# i2c-7segled-SOIC.net
KiCad netlist of a schematic drawn in EAGLE
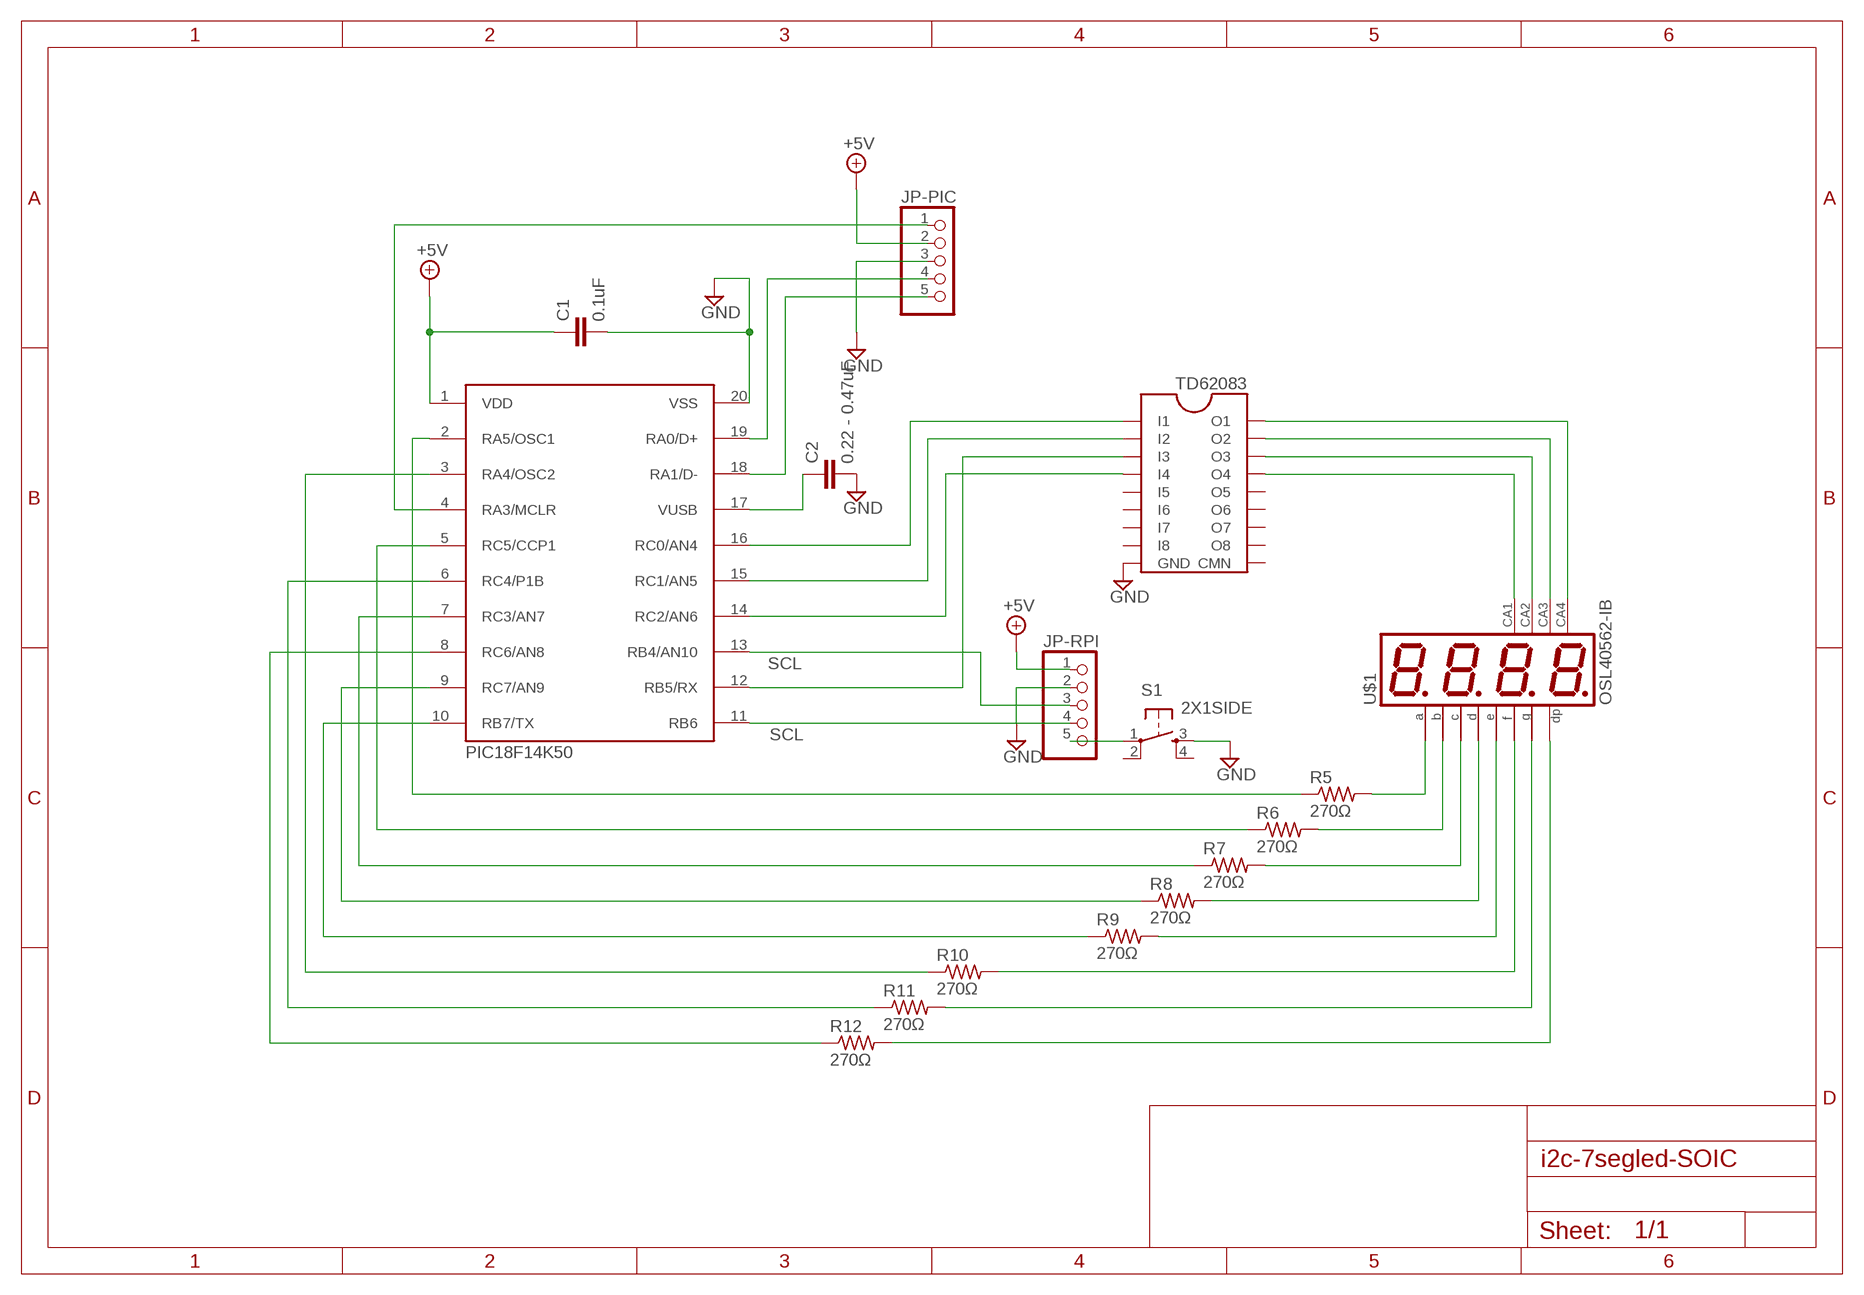
[diagram p0: schematic, sheet 1]

(export (version "E")
  (design (tool "Eeschema 10.0.6"))
  (components
    (comp (ref "C1")
      (value "0.1uF")
      (footprint "eagle-import:C0504")
      (libsource (lib "eagle-import") (part "C-EUC0504"))
    )
    (comp (ref "C2")
      (value "0.22 - 0.47uF")
      (footprint "eagle-import:C0504")
      (libsource (lib "eagle-import") (part "C-EUC0504"))
    )
    (comp (ref "JP-PIC")
      (value "PINHD-1X5")
      (footprint "eagle-import:1X05")
      (libsource (lib "eagle-import") (part "PINHD-1X5"))
    )
    (comp (ref "JP-RPI")
      (value "PINHD-1X5")
      (footprint "eagle-import:1X05")
      (libsource (lib "eagle-import") (part "PINHD-1X5"))
    )
    (comp (ref "PIC18F14K50")
      (value "PIC18F14K50-SO")
      (footprint "eagle-import:SO20")
      (libsource (lib "eagle-import") (part "PIC18F14K50-SO"))
    )
    (comp (ref "R5")
      (value "270Ω")
      (footprint "eagle-import:M0805")
      (libsource (lib "eagle-import") (part "R-US_M0805"))
    )
    (comp (ref "R6")
      (value "270Ω")
      (footprint "eagle-import:M0805")
      (libsource (lib "eagle-import") (part "R-US_M0805"))
    )
    (comp (ref "R7")
      (value "270Ω")
      (footprint "eagle-import:M0805")
      (libsource (lib "eagle-import") (part "R-US_M0805"))
    )
    (comp (ref "R8")
      (value "270Ω")
      (footprint "eagle-import:M0805")
      (libsource (lib "eagle-import") (part "R-US_M0805"))
    )
    (comp (ref "R9")
      (value "270Ω")
      (footprint "eagle-import:M0805")
      (libsource (lib "eagle-import") (part "R-US_M0805"))
    )
    (comp (ref "R10")
      (value "270Ω")
      (footprint "eagle-import:M0805")
      (libsource (lib "eagle-import") (part "R-US_M0805"))
    )
    (comp (ref "R11")
      (value "270Ω")
      (footprint "eagle-import:M0805")
      (libsource (lib "eagle-import") (part "R-US_M0805"))
    )
    (comp (ref "R12")
      (value "270Ω")
      (footprint "eagle-import:M0805")
      (libsource (lib "eagle-import") (part "R-US_M0805"))
    )
    (comp (ref "S1")
      (value "2X1SIDE")
      (footprint "eagle-import:2X1SIDE")
      (libsource (lib "eagle-import") (part "2X1SIDE"))
    )
    (comp (ref "U$1")
      (value "OSL40562-IB")
      (footprint "eagle-import:OSL40562")
      (libsource (lib "eagle-import") (part "OSL40562-?IB"))
    )
    (comp (ref "U$2")
      (value "TD62083")
      (footprint "eagle-import:SO18")
      (libsource (lib "eagle-import") (part "TD62083"))
    )
  )
  (nets
    (net (code "1") (name "+5V") (class "Default")
      (node (ref "C1") (pin "1") (pinfunction "1_1") (pintype "passive"))
      (node (ref "JP-PIC") (pin "2") (pinfunction "2_2") (pintype "passive"))
      (node (ref "JP-RPI") (pin "1") (pinfunction "1_1") (pintype "passive"))
      (node (ref "PIC18F14K50") (pin "1") (pinfunction "VDD_1") (pintype "bidirectional"))
    )
    (net (code "2") (name "/SCL") (class "Default")
      (node (ref "JP-RPI") (pin "3") (pinfunction "3_3") (pintype "passive"))
      (node (ref "PIC18F14K50") (pin "13") (pinfunction "RB4/AN10_13") (pintype "bidirectional"))
    )
    (net (code "3") (name "GND") (class "Default")
      (node (ref "C1") (pin "2") (pinfunction "2_2") (pintype "passive"))
      (node (ref "C2") (pin "2") (pinfunction "2_2") (pintype "passive"))
      (node (ref "JP-PIC") (pin "3") (pinfunction "3_3") (pintype "passive"))
      (node (ref "JP-RPI") (pin "2") (pinfunction "2_2") (pintype "passive"))
      (node (ref "PIC18F14K50") (pin "20") (pinfunction "VSS_20") (pintype "bidirectional"))
      (node (ref "S1") (pin "3") (pinfunction "S_3") (pintype "passive"))
      (node (ref "U$2") (pin "9") (pinfunction "GND_9") (pintype "passive"))
    )
    (net (code "4") (name "Net-(PIC18F14K50-RA0{slash}D+)") (class "Default")
      (node (ref "JP-PIC") (pin "4") (pinfunction "4_4") (pintype "passive"))
      (node (ref "PIC18F14K50") (pin "19") (pinfunction "RA0/D+_19") (pintype "bidirectional"))
    )
    (net (code "5") (name "Net-(PIC18F14K50-RA1{slash}D-)") (class "Default")
      (node (ref "JP-PIC") (pin "5") (pinfunction "5_5") (pintype "passive"))
      (node (ref "PIC18F14K50") (pin "18") (pinfunction "RA1/D-_18") (pintype "bidirectional"))
    )
    (net (code "6") (name "Net-(PIC18F14K50-RA3{slash}MCLR)") (class "Default")
      (node (ref "JP-PIC") (pin "1") (pinfunction "1_1") (pintype "passive"))
      (node (ref "PIC18F14K50") (pin "4") (pinfunction "RA3/MCLR_4") (pintype "bidirectional"))
    )
    (net (code "7") (name "Net-(PIC18F14K50-RA4{slash}OSC2)") (class "Default")
      (node (ref "PIC18F14K50") (pin "3") (pinfunction "RA4/OSC2_3") (pintype "bidirectional"))
      (node (ref "R10") (pin "1") (pinfunction "1_1") (pintype "passive"))
    )
    (net (code "8") (name "Net-(PIC18F14K50-RA5{slash}OSC1)") (class "Default")
      (node (ref "PIC18F14K50") (pin "2") (pinfunction "RA5/OSC1_2") (pintype "bidirectional"))
      (node (ref "R5") (pin "1") (pinfunction "1_1") (pintype "passive"))
    )
    (net (code "9") (name "Net-(PIC18F14K50-RB5{slash}RX)") (class "Default")
      (node (ref "PIC18F14K50") (pin "12") (pinfunction "RB5/RX_12") (pintype "bidirectional"))
      (node (ref "U$2") (pin "3") (pinfunction "I3_3") (pintype "passive"))
    )
    (net (code "10") (name "Net-(PIC18F14K50-RB6)") (class "Default")
      (node (ref "JP-RPI") (pin "4") (pinfunction "4_4") (pintype "passive"))
      (node (ref "PIC18F14K50") (pin "11") (pinfunction "RB6_11") (pintype "bidirectional"))
    )
    (net (code "11") (name "Net-(PIC18F14K50-RB7{slash}TX)") (class "Default")
      (node (ref "PIC18F14K50") (pin "10") (pinfunction "RB7/TX_10") (pintype "bidirectional"))
      (node (ref "R9") (pin "1") (pinfunction "1_1") (pintype "passive"))
    )
    (net (code "12") (name "Net-(PIC18F14K50-RC0{slash}AN4)") (class "Default")
      (node (ref "PIC18F14K50") (pin "16") (pinfunction "RC0/AN4_16") (pintype "bidirectional"))
      (node (ref "U$2") (pin "1") (pinfunction "I1_1") (pintype "passive"))
    )
    (net (code "13") (name "Net-(PIC18F14K50-RC1{slash}AN5)") (class "Default")
      (node (ref "PIC18F14K50") (pin "15") (pinfunction "RC1/AN5_15") (pintype "bidirectional"))
      (node (ref "U$2") (pin "2") (pinfunction "I2_2") (pintype "passive"))
    )
    (net (code "14") (name "Net-(PIC18F14K50-RC2{slash}AN6)") (class "Default")
      (node (ref "PIC18F14K50") (pin "14") (pinfunction "RC2/AN6_14") (pintype "bidirectional"))
      (node (ref "U$2") (pin "4") (pinfunction "I4_4") (pintype "passive"))
    )
    (net (code "15") (name "Net-(PIC18F14K50-RC3{slash}AN7)") (class "Default")
      (node (ref "PIC18F14K50") (pin "7") (pinfunction "RC3/AN7_7") (pintype "bidirectional"))
      (node (ref "R7") (pin "1") (pinfunction "1_1") (pintype "passive"))
    )
    (net (code "16") (name "Net-(PIC18F14K50-RC4{slash}P1B)") (class "Default")
      (node (ref "PIC18F14K50") (pin "6") (pinfunction "RC4/P1B_6") (pintype "bidirectional"))
      (node (ref "R11") (pin "1") (pinfunction "1_1") (pintype "passive"))
    )
    (net (code "17") (name "Net-(PIC18F14K50-RC5{slash}CCP1)") (class "Default")
      (node (ref "PIC18F14K50") (pin "5") (pinfunction "RC5/CCP1_5") (pintype "bidirectional"))
      (node (ref "R6") (pin "1") (pinfunction "1_1") (pintype "passive"))
    )
    (net (code "18") (name "Net-(PIC18F14K50-RC6{slash}AN8)") (class "Default")
      (node (ref "PIC18F14K50") (pin "8") (pinfunction "RC6/AN8_8") (pintype "bidirectional"))
      (node (ref "R12") (pin "1") (pinfunction "1_1") (pintype "passive"))
    )
    (net (code "19") (name "Net-(PIC18F14K50-RC7{slash}AN9)") (class "Default")
      (node (ref "PIC18F14K50") (pin "9") (pinfunction "RC7/AN9_9") (pintype "bidirectional"))
      (node (ref "R8") (pin "1") (pinfunction "1_1") (pintype "passive"))
    )
    (net (code "20") (name "Net-(PIC18F14K50-VUSB)") (class "Default")
      (node (ref "C2") (pin "1") (pinfunction "1_1") (pintype "passive"))
      (node (ref "PIC18F14K50") (pin "17") (pinfunction "VUSB_17") (pintype "bidirectional"))
    )
    (net (code "21") (name "Net-(S1-P)") (class "Default")
      (node (ref "JP-RPI") (pin "5") (pinfunction "5_5") (pintype "passive"))
      (node (ref "S1") (pin "1") (pinfunction "P_1") (pintype "passive"))
    )
    (net (code "22") (name "Net-(U$1-A)") (class "Default")
      (node (ref "R5") (pin "2") (pinfunction "2_2") (pintype "passive"))
      (node (ref "U$1") (pin "11") (pinfunction "A_11") (pintype "passive"))
    )
    (net (code "23") (name "Net-(U$1-B)") (class "Default")
      (node (ref "R6") (pin "2") (pinfunction "2_2") (pintype "passive"))
      (node (ref "U$1") (pin "7") (pinfunction "B_7") (pintype "passive"))
    )
    (net (code "24") (name "Net-(U$1-C)") (class "Default")
      (node (ref "R7") (pin "2") (pinfunction "2_2") (pintype "passive"))
      (node (ref "U$1") (pin "4") (pinfunction "C_4") (pintype "passive"))
    )
    (net (code "25") (name "Net-(U$1-D)") (class "Default")
      (node (ref "R8") (pin "2") (pinfunction "2_2") (pintype "passive"))
      (node (ref "U$1") (pin "2") (pinfunction "D_2") (pintype "passive"))
    )
    (net (code "26") (name "Net-(U$1-DP)") (class "Default")
      (node (ref "R12") (pin "2") (pinfunction "2_2") (pintype "passive"))
      (node (ref "U$1") (pin "3") (pinfunction "DP_3") (pintype "passive"))
    )
    (net (code "27") (name "Net-(U$1-E)") (class "Default")
      (node (ref "R9") (pin "2") (pinfunction "2_2") (pintype "passive"))
      (node (ref "U$1") (pin "1") (pinfunction "E_1") (pintype "passive"))
    )
    (net (code "28") (name "Net-(U$1-F)") (class "Default")
      (node (ref "R10") (pin "2") (pinfunction "2_2") (pintype "passive"))
      (node (ref "U$1") (pin "10") (pinfunction "F_10") (pintype "passive"))
    )
    (net (code "29") (name "Net-(U$1-G)") (class "Default")
      (node (ref "R11") (pin "2") (pinfunction "2_2") (pintype "passive"))
      (node (ref "U$1") (pin "5") (pinfunction "G_5") (pintype "passive"))
    )
    (net (code "30") (name "Net-(U$2-O1)") (class "Default")
      (node (ref "U$1") (pin "6") (pinfunction "CA_6") (pintype "passive"))
      (node (ref "U$2") (pin "18") (pinfunction "O1_18") (pintype "passive"))
    )
    (net (code "31") (name "Net-(U$2-O2)") (class "Default")
      (node (ref "U$1") (pin "8") (pinfunction "CA_8") (pintype "passive"))
      (node (ref "U$2") (pin "17") (pinfunction "O2_17") (pintype "passive"))
    )
    (net (code "32") (name "Net-(U$2-O3)") (class "Default")
      (node (ref "U$1") (pin "9") (pinfunction "CA_9") (pintype "passive"))
      (node (ref "U$2") (pin "16") (pinfunction "O3_16") (pintype "passive"))
    )
    (net (code "33") (name "Net-(U$2-O4)") (class "Default")
      (node (ref "U$1") (pin "12") (pinfunction "CA_12") (pintype "passive"))
      (node (ref "U$2") (pin "15") (pinfunction "O4_15") (pintype "passive"))
    )
    (net (code "34") (name "unconnected-(S1-P1-Pad2)") (class "Default")
      (node (ref "S1") (pin "2") (pinfunction "P1_2") (pintype "passive"))
    )
    (net (code "35") (name "unconnected-(S1-S1-Pad4)") (class "Default")
      (node (ref "S1") (pin "4") (pinfunction "S1_4") (pintype "passive"))
    )
    (net (code "36") (name "unconnected-(U$2-CMN-Pad10)") (class "Default")
      (node (ref "U$2") (pin "10") (pinfunction "CMN_10") (pintype "passive"))
    )
    (net (code "37") (name "unconnected-(U$2-I5-Pad5)") (class "Default")
      (node (ref "U$2") (pin "5") (pinfunction "I5_5") (pintype "passive"))
    )
    (net (code "38") (name "unconnected-(U$2-I6-Pad6)") (class "Default")
      (node (ref "U$2") (pin "6") (pinfunction "I6_6") (pintype "passive"))
    )
    (net (code "39") (name "unconnected-(U$2-I7-Pad7)") (class "Default")
      (node (ref "U$2") (pin "7") (pinfunction "I7_7") (pintype "passive"))
    )
    (net (code "40") (name "unconnected-(U$2-I8-Pad8)") (class "Default")
      (node (ref "U$2") (pin "8") (pinfunction "I8_8") (pintype "passive"))
    )
    (net (code "41") (name "unconnected-(U$2-O5-Pad14)") (class "Default")
      (node (ref "U$2") (pin "14") (pinfunction "O5_14") (pintype "passive"))
    )
    (net (code "42") (name "unconnected-(U$2-O6-Pad13)") (class "Default")
      (node (ref "U$2") (pin "13") (pinfunction "O6_13") (pintype "passive"))
    )
    (net (code "43") (name "unconnected-(U$2-O7-Pad12)") (class "Default")
      (node (ref "U$2") (pin "12") (pinfunction "O7_12") (pintype "passive"))
    )
    (net (code "44") (name "unconnected-(U$2-O8-Pad11)") (class "Default")
      (node (ref "U$2") (pin "11") (pinfunction "O8_11") (pintype "passive"))
    )
  )
)
